# SoC_PS_Config_503.net
KiCad netlist of a schematic drawn in Altium Designer
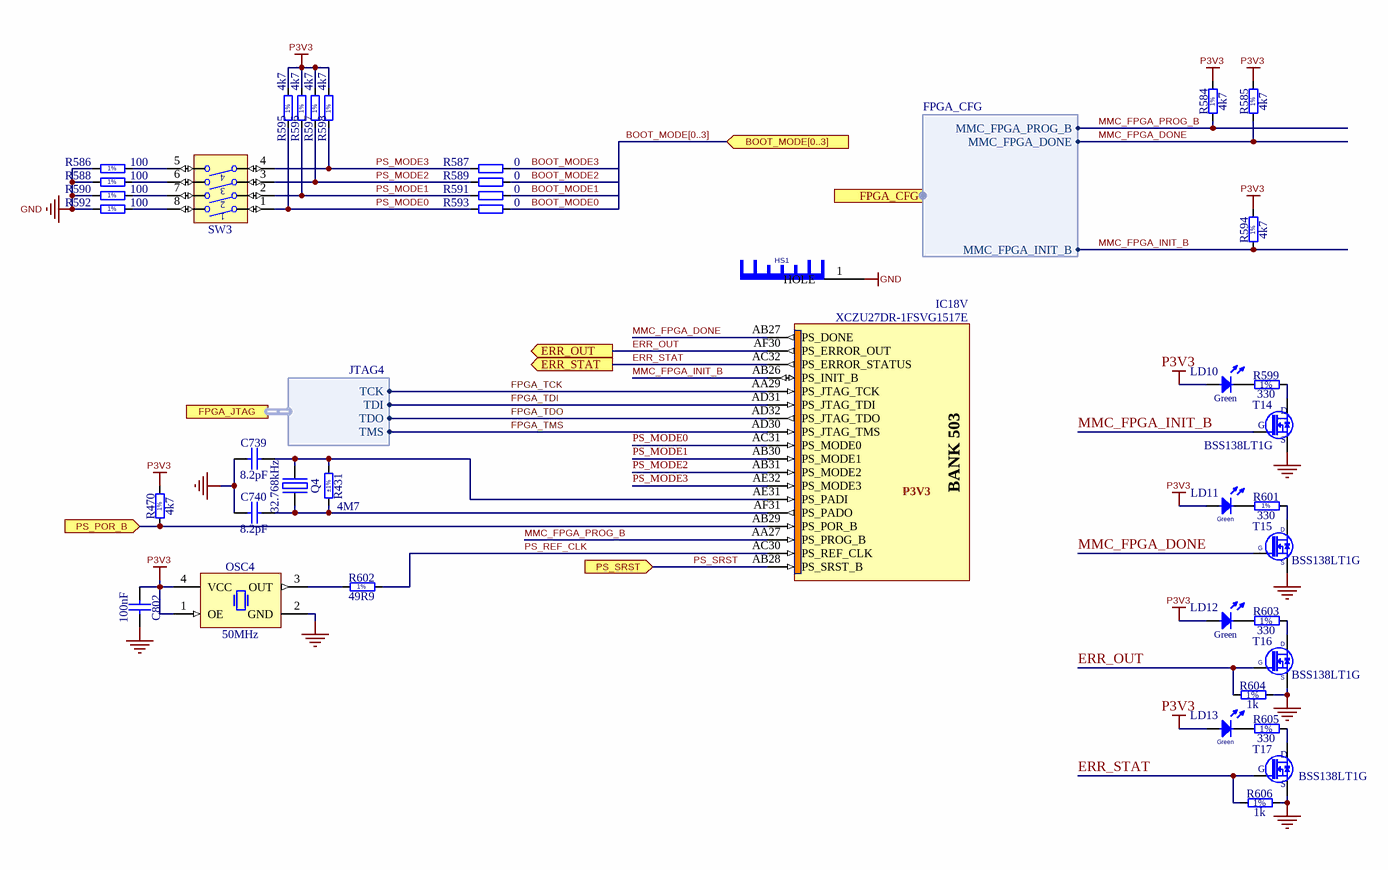
[diagram p0: SoC_PS_Config_503.SchDoc]

(export (version "E")
  (design (tool "Eeschema 10.0.6"))
  (components
    (comp (ref "C739")
      (value "8.2pF")
      (footprint "CAPC1005X55N")
      (description "Non-polarised capacitor")
      (fields
        (field (name "PART NUMBER") "CC0402_8.2PF_50V_0.1PF_NP0_AVX_04025A8R2BAT2A")
        (field (name "VOLTAGE") "50V")
        (field (name "AUTHOR") "CERN DEM BC")
      )
      (libsource (lib "Capacitors") (part "Capacitor - non polarized"))
    )
    (comp (ref "C740")
      (value "8.2pF")
      (footprint "CAPC1005X55N")
      (description "Non-polarised capacitor")
      (fields
        (field (name "PART NUMBER") "CC0402_8.2PF_50V_0.1PF_NP0_AVX_04025A8R2BAT2A")
        (field (name "VOLTAGE") "50V")
        (field (name "AUTHOR") "CERN DEM BC")
      )
      (libsource (lib "Capacitors") (part "Capacitor - non polarized"))
    )
    (comp (ref "C802")
      (value "100nF")
      (footprint "CAPC0603X33N")
      (description "Non-polarised capacitor")
      (fields
        (field (name "MANUFACTURER PART NUMBER") "CC0201_100NF_6.3V_10%_X5R")
        (field (name "MANUFACTURER") "GENERIC")
        (field (name "AUTHOR") "CERN DEM JLC")
      )
      (libsource (lib "Capacitors") (part "Capacitor - non polarized"))
    )
    (comp (ref "HS1")
      (value "Heat Sink No Pad")
      (footprint "HSINK_WAKEFIELD_SKV585811-CU")
      (description "Heat Sink Without Pad")
      (fields
        (field (name "PART NUMBER") "HSINK_WAKEFIELD_SKV585811-CU")
        (field (name "MANUFACTURER") "WAKEFIELD-VETTE")
        (field (name "AUTHOR") "CERN DEM JMW")
      )
      (libsource (lib "Eletro-mechanical") (part "Heat Sink No Pad"))
    )
    (comp (ref "IC18")
      (value "XCZU27DR-1FSVG1517E")
      (footprint "XILINX_FSVG1517 (XCZU27DR)")
      (fields (field (name "MANUFACTURER") "XILINX") (field (name "AUTHOR") "CERN DEM MR"))
      (libsource (lib "ICs And Semiconductors") (part "XCZU27DR-1FSVG1517E"))
    )
    (comp (ref "LD10")
      (value "Green")
      (footprint "LED_AVAGO_HSME-C120")
      (description "LED Green 1C 2A")
      (fields
        (field (name "MANUFACTURER PART NUMBER") "HSME-C120")
        (field (name "MANUFACTURER") "AVAGO TECHNOLOGIES")
        (field (name "AUTHOR") "CERN DEM JMW")
      )
      (libsource (lib "ICs And Semiconductors") (part "LED Green 1C 2A"))
    )
    (comp (ref "LD11")
      (value "Green")
      (footprint "LED_AVAGO_HSME-C120")
      (description "LED Green 1C 2A")
      (fields
        (field (name "MANUFACTURER PART NUMBER") "HSME-C120")
        (field (name "MANUFACTURER") "AVAGO TECHNOLOGIES")
        (field (name "AUTHOR") "CERN DEM JMW")
      )
      (libsource (lib "ICs And Semiconductors") (part "LED Green 1C 2A"))
    )
    (comp (ref "LD12")
      (value "Green")
      (footprint "LED_KINGBRIGHT_KPH-1608CGCK")
      (description "LED Green 1C 2A")
      (fields
        (field (name "MANUFACTURER PART NUMBER") "KPH-1608CGCK")
        (field (name "MANUFACTURER") "KINGBRIGHT")
        (field (name "AUTHOR") "CERN DEM JLC")
      )
      (libsource (lib "ICs And Semiconductors") (part "LED Green 1C 2A"))
    )
    (comp (ref "LD13")
      (value "Green")
      (footprint "LED_KINGBRIGHT_KPH-1608CGCK")
      (description "LED Green 1C 2A")
      (fields
        (field (name "MANUFACTURER PART NUMBER") "KPH-1608CGCK")
        (field (name "MANUFACTURER") "KINGBRIGHT")
        (field (name "AUTHOR") "CERN DEM JLC")
      )
      (libsource (lib "ICs And Semiconductors") (part "LED Green 1C 2A"))
    )
    (comp (ref "OSC4")
      (value "50MHz")
      (footprint "OSCSC254P320X500X130-4N")
      (description "Oscillator 4 pins 1=OE 2=GND 3=OUT 4=VCC")
      (fields
        (field (name "PART NUMBER") "OSC_50MHZ_CTS_636L3I050M00000")
        (field (name "MANUFACTURER") "CTS ELECTRONIC COMPONENTS")
        (field (name "AUTHOR") "CERN DEM JMW")
      )
      (libsource (lib "ICs And Semiconductors") (part "Oscillator 1OE 2GND 3OUT 4VCC"))
    )
    (comp (ref "Q4")
      (value "32.768kHz")
      (footprint "XTAL_ABRACON_ABS06")
      (description "Quartz Crystal")
      (fields
        (field (name "MANUFACTURER PART NUMBER") "ABS06-32.768kHz-9")
        (field (name "MANUFACTURER") "ABRACON")
        (field (name "AUTHOR") "CERN DEM JMW")
      )
      (libsource (lib "ICs And Semiconductors") (part "Quartz Crystal"))
    )
    (comp (ref "R431")
      (value "4M7")
      (footprint "RESC1005X40N")
      (description "Resistor - 1%")
      (fields
        (field (name "TOLERANCE") "±1%")
        (field (name "PART NUMBER") "R0402_4M7_1%_0.063W_100PPM")
        (field (name "POWER") "0.063W")
        (field (name "AUTHOR") "CERN DEM BC")
      )
      (libsource (lib "Resistors") (part "Resistor - 1%"))
    )
    (comp (ref "R470")
      (value "4k7")
      (footprint "RESC1005X40N")
      (description "Resistor - 1%")
      (fields
        (field (name "MANUFACTURER PART NUMBER") "R0402_4K7_1%_0.0625W_100PPM")
        (field (name "MANUFACTURER") "GENERIC")
        (field (name "AUTHOR") "CERN DEM JLC")
      )
      (libsource (lib "Resistors") (part "Resistor - 1%"))
    )
    (comp (ref "R584")
      (value "4k7")
      (footprint "RESC1005X40N")
      (description "Resistor - 1%")
      (fields
        (field (name "MANUFACTURER PART NUMBER") "R0402_4K7_1%_0.0625W_100PPM")
        (field (name "MANUFACTURER") "GENERIC")
        (field (name "AUTHOR") "CERN DEM JLC")
      )
      (libsource (lib "Resistors") (part "Resistor - 1%"))
    )
    (comp (ref "R585")
      (value "4k7")
      (footprint "RESC1005X40N")
      (description "Resistor - 1%")
      (fields
        (field (name "MANUFACTURER PART NUMBER") "R0402_4K7_1%_0.0625W_100PPM")
        (field (name "MANUFACTURER") "GENERIC")
        (field (name "AUTHOR") "CERN DEM JLC")
      )
      (libsource (lib "Resistors") (part "Resistor - 1%"))
    )
    (comp (ref "R586")
      (value "100")
      (footprint "RESC1005X40N")
      (description "Resistor - 1%")
      (fields
        (field (name "MANUFACTURER PART NUMBER") "R0402_100R_1%_0.1W_100PPM_50V")
        (field (name "MANUFACTURER") "GENERIC")
        (field (name "AUTHOR") "CERN DEM JLC")
      )
      (libsource (lib "Resistors") (part "Resistor - 1%"))
    )
    (comp (ref "R587")
      (value "0")
      (footprint "RESC1005X40N")
      (description "Resistor")
      (fields
        (field (name "MANUFACTURER PART NUMBER") "R0402_0R_JUMPER")
        (field (name "MANUFACTURER") "GENERIC")
        (field (name "AUTHOR") "CERN DEM JLC")
      )
      (libsource (lib "Resistors") (part "Resistor"))
    )
    (comp (ref "R588")
      (value "100")
      (footprint "RESC1005X40N")
      (description "Resistor - 1%")
      (fields
        (field (name "MANUFACTURER PART NUMBER") "R0402_100R_1%_0.1W_100PPM_50V")
        (field (name "MANUFACTURER") "GENERIC")
        (field (name "AUTHOR") "CERN DEM JLC")
      )
      (libsource (lib "Resistors") (part "Resistor - 1%"))
    )
    (comp (ref "R589")
      (value "0")
      (footprint "RESC1005X40N")
      (description "Resistor")
      (fields
        (field (name "MANUFACTURER PART NUMBER") "R0402_0R_JUMPER")
        (field (name "MANUFACTURER") "GENERIC")
        (field (name "AUTHOR") "CERN DEM JLC")
      )
      (libsource (lib "Resistors") (part "Resistor"))
    )
    (comp (ref "R590")
      (value "100")
      (footprint "RESC1005X40N")
      (description "Resistor - 1%")
      (fields
        (field (name "MANUFACTURER PART NUMBER") "R0402_100R_1%_0.1W_100PPM_50V")
        (field (name "MANUFACTURER") "GENERIC")
        (field (name "AUTHOR") "CERN DEM JLC")
      )
      (libsource (lib "Resistors") (part "Resistor - 1%"))
    )
    (comp (ref "R591")
      (value "0")
      (footprint "RESC1005X40N")
      (description "Resistor")
      (fields
        (field (name "MANUFACTURER PART NUMBER") "R0402_0R_JUMPER")
        (field (name "MANUFACTURER") "GENERIC")
        (field (name "AUTHOR") "CERN DEM JLC")
      )
      (libsource (lib "Resistors") (part "Resistor"))
    )
    (comp (ref "R592")
      (value "100")
      (footprint "RESC1005X40N")
      (description "Resistor - 1%")
      (fields
        (field (name "MANUFACTURER PART NUMBER") "R0402_100R_1%_0.1W_100PPM_50V")
        (field (name "MANUFACTURER") "GENERIC")
        (field (name "AUTHOR") "CERN DEM JLC")
      )
      (libsource (lib "Resistors") (part "Resistor - 1%"))
    )
    (comp (ref "R593")
      (value "0")
      (footprint "RESC1005X40N")
      (description "Resistor")
      (fields
        (field (name "MANUFACTURER PART NUMBER") "R0402_0R_JUMPER")
        (field (name "MANUFACTURER") "GENERIC")
        (field (name "AUTHOR") "CERN DEM JLC")
      )
      (libsource (lib "Resistors") (part "Resistor"))
    )
    (comp (ref "R594")
      (value "4k7")
      (footprint "RESC1005X40N")
      (description "Resistor - 1%")
      (fields
        (field (name "MANUFACTURER PART NUMBER") "R0402_4K7_1%_0.0625W_100PPM")
        (field (name "MANUFACTURER") "GENERIC")
        (field (name "AUTHOR") "CERN DEM JLC")
      )
      (libsource (lib "Resistors") (part "Resistor - 1%"))
    )
    (comp (ref "R595")
      (value "4k7")
      (footprint "RESC1005X40N")
      (description "Resistor - 1%")
      (fields
        (field (name "PART NUMBER") "R0402_4K7_1%_0.0625W_100PPM")
        (field (name "POWER") "0.0625W")
        (field (name "AUTHOR") "CERN DEM JLC")
      )
      (libsource (lib "Resistors") (part "Resistor - 1%"))
    )
    (comp (ref "R596")
      (value "4k7")
      (footprint "RESC1005X40N")
      (description "Resistor - 1%")
      (fields
        (field (name "PART NUMBER") "R0402_4K7_1%_0.0625W_100PPM")
        (field (name "POWER") "0.0625W")
        (field (name "AUTHOR") "CERN DEM JLC")
      )
      (libsource (lib "Resistors") (part "Resistor - 1%"))
    )
    (comp (ref "R597")
      (value "4k7")
      (footprint "RESC1005X40N")
      (description "Resistor - 1%")
      (fields
        (field (name "PART NUMBER") "R0402_4K7_1%_0.0625W_100PPM")
        (field (name "POWER") "0.0625W")
        (field (name "AUTHOR") "CERN DEM JLC")
      )
      (libsource (lib "Resistors") (part "Resistor - 1%"))
    )
    (comp (ref "R598")
      (value "4k7")
      (footprint "RESC1005X40N")
      (description "Resistor - 1%")
      (fields
        (field (name "PART NUMBER") "R0402_4K7_1%_0.0625W_100PPM")
        (field (name "POWER") "0.0625W")
        (field (name "AUTHOR") "CERN DEM JLC")
      )
      (libsource (lib "Resistors") (part "Resistor - 1%"))
    )
    (comp (ref "R599")
      (value "330")
      (footprint "RESC1005X40N")
      (description "Resistor - 1%")
      (fields
        (field (name "MANUFACTURER PART NUMBER") "R0402_330R_1%_0.0625W_100PPM")
        (field (name "MANUFACTURER") "GENERIC")
        (field (name "AUTHOR") "CERN DEM JLC")
      )
      (libsource (lib "Resistors") (part "Resistor - 1%"))
    )
    (comp (ref "R601")
      (value "330")
      (footprint "RESC1005X40N")
      (description "Resistor - 1%")
      (fields
        (field (name "MANUFACTURER PART NUMBER") "R0402_330R_1%_0.0625W_100PPM")
        (field (name "MANUFACTURER") "GENERIC")
        (field (name "AUTHOR") "CERN DEM JLC")
      )
      (libsource (lib "Resistors") (part "Resistor - 1%"))
    )
    (comp (ref "R602")
      (value "49R9")
      (footprint "RESC1005X40N")
      (description "Resistor - 1%")
      (fields
        (field (name "MANUFACTURER PART NUMBER") "R0402_49R9_1%_0.0625W_100PPM")
        (field (name "MANUFACTURER") "GENERIC")
        (field (name "AUTHOR") "CERN DEM JLC")
      )
      (libsource (lib "Resistors") (part "Resistor - 1%"))
    )
    (comp (ref "R603")
      (value "330")
      (footprint "RESC1005X40N")
      (description "Resistor - 1%")
      (fields
        (field (name "MANUFACTURER PART NUMBER") "R0402_330R_1%_0.0625W_100PPM")
        (field (name "MANUFACTURER") "GENERIC")
        (field (name "AUTHOR") "CERN DEM JLC")
      )
      (libsource (lib "Resistors") (part "Resistor - 1%"))
    )
    (comp (ref "R604")
      (value "1k")
      (footprint "RESC1005X40N")
      (description "Resistor - 1%")
      (fields
        (field (name "MANUFACTURER PART NUMBER") "R0402_1K_1%_0.0625W_100PPM")
        (field (name "MANUFACTURER") "GENERIC")
        (field (name "AUTHOR") "CERN DEM JLC")
      )
      (libsource (lib "Resistors") (part "Resistor - 1%"))
    )
    (comp (ref "R605")
      (value "330")
      (footprint "RESC1005X40N")
      (description "Resistor - 1%")
      (fields
        (field (name "MANUFACTURER PART NUMBER") "R0402_330R_1%_0.0625W_100PPM")
        (field (name "MANUFACTURER") "GENERIC")
        (field (name "AUTHOR") "CERN DEM JLC")
      )
      (libsource (lib "Resistors") (part "Resistor - 1%"))
    )
    (comp (ref "R606")
      (value "1k")
      (footprint "RESC1005X40N")
      (description "Resistor - 1%")
      (fields
        (field (name "MANUFACTURER PART NUMBER") "R0402_1K_1%_0.0625W_100PPM")
        (field (name "MANUFACTURER") "GENERIC")
        (field (name "AUTHOR") "CERN DEM JLC")
      )
      (libsource (lib "Resistors") (part "Resistor - 1%"))
    )
    (comp (ref "SW3")
      (value "Switch")
      (footprint "SW_TYCO_1571983-4")
      (description "4 Ways SPST DIP Switch")
      (fields
        (field (name "MANUFACTURER PART NUMBER") "1571983-4 or GDH04S04")
        (field (name "MANUFACTURER") "TYCO")
        (field (name "AUTHOR") "CERN DEM JLC")
      )
      (libsource (lib "Eletro-mechanical") (part "SW 4x SPST DIP Switch"))
    )
    (comp (ref "T14")
      (value "BSS138LT1G")
      (footprint "SOT95P240X110-3N")
      (description "N-CHANNEL MOSFET WITH DIODE")
      (fields (field (name "MANUFACTURER") "ON SEMICONDUCTOR") (field (name "AUTHOR") "CERN DEM JLC"))
      (libsource (lib "ICs And Semiconductors") (part "N-MOSFET-D 1G 2S 3D"))
    )
    (comp (ref "T15")
      (value "BSS138LT1G")
      (footprint "SOT95P240X110-3N")
      (description "N-CHANNEL MOSFET WITH DIODE")
      (fields (field (name "MANUFACTURER") "ON SEMICONDUCTOR") (field (name "AUTHOR") "CERN DEM JLC"))
      (libsource (lib "ICs And Semiconductors") (part "N-MOSFET-D 1G 2S 3D"))
    )
    (comp (ref "T16")
      (value "BSS138LT1G")
      (footprint "SOT95P240X110-3N")
      (description "N-CHANNEL MOSFET WITH DIODE")
      (fields (field (name "MANUFACTURER") "ON SEMICONDUCTOR") (field (name "AUTHOR") "CERN DEM JLC"))
      (libsource (lib "ICs And Semiconductors") (part "N-MOSFET-D 1G 2S 3D"))
    )
    (comp (ref "T17")
      (value "BSS138LT1G")
      (footprint "SOT95P240X110-3N")
      (description "N-CHANNEL MOSFET WITH DIODE")
      (fields (field (name "MANUFACTURER") "ON SEMICONDUCTOR") (field (name "AUTHOR") "CERN DEM JLC"))
      (libsource (lib "ICs And Semiconductors") (part "N-MOSFET-D 1G 2S 3D"))
    )
  )
  (nets
    (net (code "3") (name "/BOOT_MODE0") (class "Default")
      (node (ref "R593") (pin "2") (pinfunction "2_2") (pintype "passive"))
    )
    (net (code "4") (name "/BOOT_MODE1") (class "Default")
      (node (ref "R591") (pin "2") (pinfunction "2_2") (pintype "passive"))
    )
    (net (code "5") (name "/BOOT_MODE2") (class "Default")
      (node (ref "R589") (pin "2") (pinfunction "2_2") (pintype "passive"))
    )
    (net (code "6") (name "/BOOT_MODE3") (class "Default")
      (node (ref "R587") (pin "2") (pinfunction "2_2") (pintype "passive"))
    )
    (net (code "8") (name "/ERR_OUT") (class "Default")
      (node (ref "IC18") (pin "AF30") (pinfunction "PS_ERROR_OUT_AF30") (pintype "output"))
      (node (ref "R604") (pin "1") (pinfunction "1_1") (pintype "passive"))
      (node (ref "T16") (pin "1") (pinfunction "G_1") (pintype "passive"))
    )
    (net (code "9") (name "/ERR_STAT") (class "Default")
      (node (ref "IC18") (pin "AC32") (pinfunction "PS_ERROR_STATUS_AC32") (pintype "output"))
      (node (ref "R606") (pin "1") (pinfunction "1_1") (pintype "passive"))
      (node (ref "T17") (pin "1") (pinfunction "G_1") (pintype "passive"))
    )
    (net (code "10") (name "/FPGA_TCK") (class "Default")
      (node (ref "IC18") (pin "AA29") (pinfunction "PS_JTAG_TCK_AA29") (pintype "input"))
    )
    (net (code "11") (name "/FPGA_TDI") (class "Default")
      (node (ref "IC18") (pin "AD31") (pinfunction "PS_JTAG_TDI_AD31") (pintype "input"))
    )
    (net (code "12") (name "/FPGA_TDO") (class "Default")
      (node (ref "IC18") (pin "AD32") (pinfunction "PS_JTAG_TDO_AD32") (pintype "output"))
    )
    (net (code "13") (name "/FPGA_TMS") (class "Default")
      (node (ref "IC18") (pin "AD30") (pinfunction "PS_JTAG_TMS_AD30") (pintype "input"))
    )
    (net (code "14") (name "/MMC_FPGA_DONE") (class "Default")
      (node (ref "IC18") (pin "AB27") (pinfunction "PS_DONE_AB27") (pintype "output"))
      (node (ref "R585") (pin "1") (pinfunction "1_1") (pintype "passive"))
      (node (ref "T15") (pin "1") (pinfunction "G_1") (pintype "passive"))
    )
    (net (code "15") (name "/MMC_FPGA_INIT_B") (class "Default")
      (node (ref "IC18") (pin "AB26") (pinfunction "PS_INIT_B_AB26") (pintype "bidirectional"))
      (node (ref "R594") (pin "1") (pinfunction "1_1") (pintype "passive"))
      (node (ref "T14") (pin "1") (pinfunction "G_1") (pintype "passive"))
    )
    (net (code "16") (name "/MMC_FPGA_PROG_B") (class "Default")
      (node (ref "IC18") (pin "AA27") (pinfunction "PS_PROG_B_AA27") (pintype "input"))
      (node (ref "R584") (pin "1") (pinfunction "1_1") (pintype "passive"))
    )
    (net (code "17") (name "/PS_MODE0") (class "Default")
      (node (ref "IC18") (pin "AC31") (pinfunction "PS_MODE0_AC31") (pintype "input"))
      (node (ref "R593") (pin "1") (pinfunction "1_1") (pintype "passive"))
      (node (ref "R595") (pin "1") (pinfunction "1_1") (pintype "passive"))
      (node (ref "SW3") (pin "1") (pinfunction "1_1") (pintype "bidirectional"))
    )
    (net (code "18") (name "/PS_MODE1") (class "Default")
      (node (ref "IC18") (pin "AB30") (pinfunction "PS_MODE1_AB30") (pintype "input"))
      (node (ref "R591") (pin "1") (pinfunction "1_1") (pintype "passive"))
      (node (ref "R596") (pin "1") (pinfunction "1_1") (pintype "passive"))
      (node (ref "SW3") (pin "2") (pinfunction "2_2") (pintype "bidirectional"))
    )
    (net (code "19") (name "/PS_MODE2") (class "Default")
      (node (ref "IC18") (pin "AB31") (pinfunction "PS_MODE2_AB31") (pintype "input"))
      (node (ref "R589") (pin "1") (pinfunction "1_1") (pintype "passive"))
      (node (ref "R597") (pin "1") (pinfunction "1_1") (pintype "passive"))
      (node (ref "SW3") (pin "3") (pinfunction "3_3") (pintype "bidirectional"))
    )
    (net (code "20") (name "/PS_MODE3") (class "Default")
      (node (ref "IC18") (pin "AE32") (pinfunction "PS_MODE3_AE32") (pintype "input"))
      (node (ref "R587") (pin "1") (pinfunction "1_1") (pintype "passive"))
      (node (ref "R598") (pin "1") (pinfunction "1_1") (pintype "passive"))
      (node (ref "SW3") (pin "4") (pinfunction "4_4") (pintype "bidirectional"))
    )
    (net (code "21") (name "/PS_POR_B") (class "Default")
      (node (ref "IC18") (pin "AB29") (pinfunction "PS_POR_B_AB29") (pintype "input"))
      (node (ref "R470") (pin "1") (pinfunction "1_1") (pintype "passive"))
    )
    (net (code "22") (name "/PS_REF_CLK") (class "Default")
      (node (ref "IC18") (pin "AC30") (pinfunction "PS_REF_CLK_AC30") (pintype "input"))
      (node (ref "R602") (pin "2") (pinfunction "2_2") (pintype "passive"))
    )
    (net (code "23") (name "/PS_SRST") (class "Default")
      (node (ref "IC18") (pin "AB28") (pinfunction "PS_SRST_B_AB28") (pintype "input"))
    )
    (net (code "26") (name "GND") (class "Default")
      (node (ref "C739") (pin "1") (pinfunction "1_1") (pintype "passive"))
      (node (ref "C740") (pin "1") (pinfunction "1_1") (pintype "passive"))
      (node (ref "C802") (pin "2") (pinfunction "2_2") (pintype "passive"))
      (node (ref "HS1") (pin "1") (pinfunction "HOLE_1") (pintype "passive"))
      (node (ref "OSC4") (pin "2") (pinfunction "GND_2") (pintype "power_in"))
      (node (ref "R586") (pin "1") (pinfunction "1_1") (pintype "passive"))
      (node (ref "R588") (pin "1") (pinfunction "1_1") (pintype "passive"))
      (node (ref "R590") (pin "1") (pinfunction "1_1") (pintype "passive"))
      (node (ref "R592") (pin "1") (pinfunction "1_1") (pintype "passive"))
      (node (ref "R604") (pin "2") (pinfunction "2_2") (pintype "passive"))
      (node (ref "R606") (pin "2") (pinfunction "2_2") (pintype "passive"))
      (node (ref "T14") (pin "2") (pinfunction "S_2") (pintype "passive"))
      (node (ref "T15") (pin "2") (pinfunction "S_2") (pintype "passive"))
      (node (ref "T16") (pin "2") (pinfunction "S_2") (pintype "passive"))
      (node (ref "T17") (pin "2") (pinfunction "S_2") (pintype "passive"))
    )
    (net (code "27") (name "Net-(IC18V-PS_PADI)") (class "Default")
      (node (ref "C739") (pin "2") (pinfunction "2_2") (pintype "passive"))
      (node (ref "IC18") (pin "AE31") (pinfunction "PS_PADI_AE31") (pintype "input"))
      (node (ref "Q4") (pin "1") (pinfunction "OSC1_1") (pintype "passive"))
      (node (ref "R431") (pin "1") (pinfunction "1_1") (pintype "passive"))
    )
    (net (code "28") (name "Net-(IC18V-PS_PADO)") (class "Default")
      (node (ref "C740") (pin "2") (pinfunction "2_2") (pintype "passive"))
      (node (ref "IC18") (pin "AF31") (pinfunction "PS_PADO_AF31") (pintype "output"))
      (node (ref "Q4") (pin "2") (pinfunction "OSC2_2") (pintype "passive"))
      (node (ref "R431") (pin "2") (pinfunction "2_2") (pintype "passive"))
    )
    (net (code "29") (name "Net-(LD10-C)") (class "Default")
      (node (ref "LD10") (pin "1") (pinfunction "C_1") (pintype "passive"))
      (node (ref "R599") (pin "1") (pinfunction "1_1") (pintype "passive"))
    )
    (net (code "30") (name "Net-(LD11-C)") (class "Default")
      (node (ref "LD11") (pin "1") (pinfunction "C_1") (pintype "passive"))
      (node (ref "R601") (pin "1") (pinfunction "1_1") (pintype "passive"))
    )
    (net (code "31") (name "Net-(LD12-C)") (class "Default")
      (node (ref "LD12") (pin "1") (pinfunction "C_1") (pintype "passive"))
      (node (ref "R603") (pin "1") (pinfunction "1_1") (pintype "passive"))
    )
    (net (code "32") (name "Net-(LD13-C)") (class "Default")
      (node (ref "LD13") (pin "1") (pinfunction "C_1") (pintype "passive"))
      (node (ref "R605") (pin "1") (pinfunction "1_1") (pintype "passive"))
    )
    (net (code "33") (name "Net-(OSC4-OUT)") (class "Default")
      (node (ref "OSC4") (pin "3") (pinfunction "OUT_3") (pintype "output"))
      (node (ref "R602") (pin "1") (pinfunction "1_1") (pintype "passive"))
    )
    (net (code "34") (name "Net-(R586-Pad2)") (class "Default")
      (node (ref "R586") (pin "2") (pinfunction "2_2") (pintype "passive"))
      (node (ref "SW3") (pin "5") (pinfunction "5_5") (pintype "bidirectional"))
    )
    (net (code "35") (name "Net-(R588-Pad2)") (class "Default")
      (node (ref "R588") (pin "2") (pinfunction "2_2") (pintype "passive"))
      (node (ref "SW3") (pin "6") (pinfunction "6_6") (pintype "bidirectional"))
    )
    (net (code "36") (name "Net-(R590-Pad2)") (class "Default")
      (node (ref "R590") (pin "2") (pinfunction "2_2") (pintype "passive"))
      (node (ref "SW3") (pin "7") (pinfunction "7_7") (pintype "bidirectional"))
    )
    (net (code "37") (name "Net-(R592-Pad2)") (class "Default")
      (node (ref "R592") (pin "2") (pinfunction "2_2") (pintype "passive"))
      (node (ref "SW3") (pin "8") (pinfunction "8_8") (pintype "bidirectional"))
    )
    (net (code "38") (name "Net-(T14-D)") (class "Default")
      (node (ref "R599") (pin "2") (pinfunction "2_2") (pintype "passive"))
      (node (ref "T14") (pin "3") (pinfunction "D_3") (pintype "passive"))
    )
    (net (code "39") (name "Net-(T15-D)") (class "Default")
      (node (ref "R601") (pin "2") (pinfunction "2_2") (pintype "passive"))
      (node (ref "T15") (pin "3") (pinfunction "D_3") (pintype "passive"))
    )
    (net (code "40") (name "Net-(T16-D)") (class "Default")
      (node (ref "R603") (pin "2") (pinfunction "2_2") (pintype "passive"))
      (node (ref "T16") (pin "3") (pinfunction "D_3") (pintype "passive"))
    )
    (net (code "41") (name "Net-(T17-D)") (class "Default")
      (node (ref "R605") (pin "2") (pinfunction "2_2") (pintype "passive"))
      (node (ref "T17") (pin "3") (pinfunction "D_3") (pintype "passive"))
    )
    (net (code "42") (name "P3V3") (class "Default")
      (node (ref "C802") (pin "1") (pinfunction "1_1") (pintype "passive"))
      (node (ref "LD10") (pin "2") (pinfunction "A_2") (pintype "passive"))
      (node (ref "LD11") (pin "2") (pinfunction "A_2") (pintype "passive"))
      (node (ref "LD12") (pin "2") (pinfunction "A_2") (pintype "passive"))
      (node (ref "LD13") (pin "2") (pinfunction "A_2") (pintype "passive"))
      (node (ref "OSC4") (pin "1") (pinfunction "OE_1") (pintype "input"))
      (node (ref "OSC4") (pin "4") (pinfunction "VCC_4") (pintype "power_in"))
      (node (ref "R470") (pin "2") (pinfunction "2_2") (pintype "passive"))
      (node (ref "R584") (pin "2") (pinfunction "2_2") (pintype "passive"))
      (node (ref "R585") (pin "2") (pinfunction "2_2") (pintype "passive"))
      (node (ref "R594") (pin "2") (pinfunction "2_2") (pintype "passive"))
      (node (ref "R595") (pin "2") (pinfunction "2_2") (pintype "passive"))
      (node (ref "R596") (pin "2") (pinfunction "2_2") (pintype "passive"))
      (node (ref "R597") (pin "2") (pinfunction "2_2") (pintype "passive"))
      (node (ref "R598") (pin "2") (pinfunction "2_2") (pintype "passive"))
    )
  )
)
